# cerebro5_8.net
KiCad netlist of a schematic drawn in EAGLE
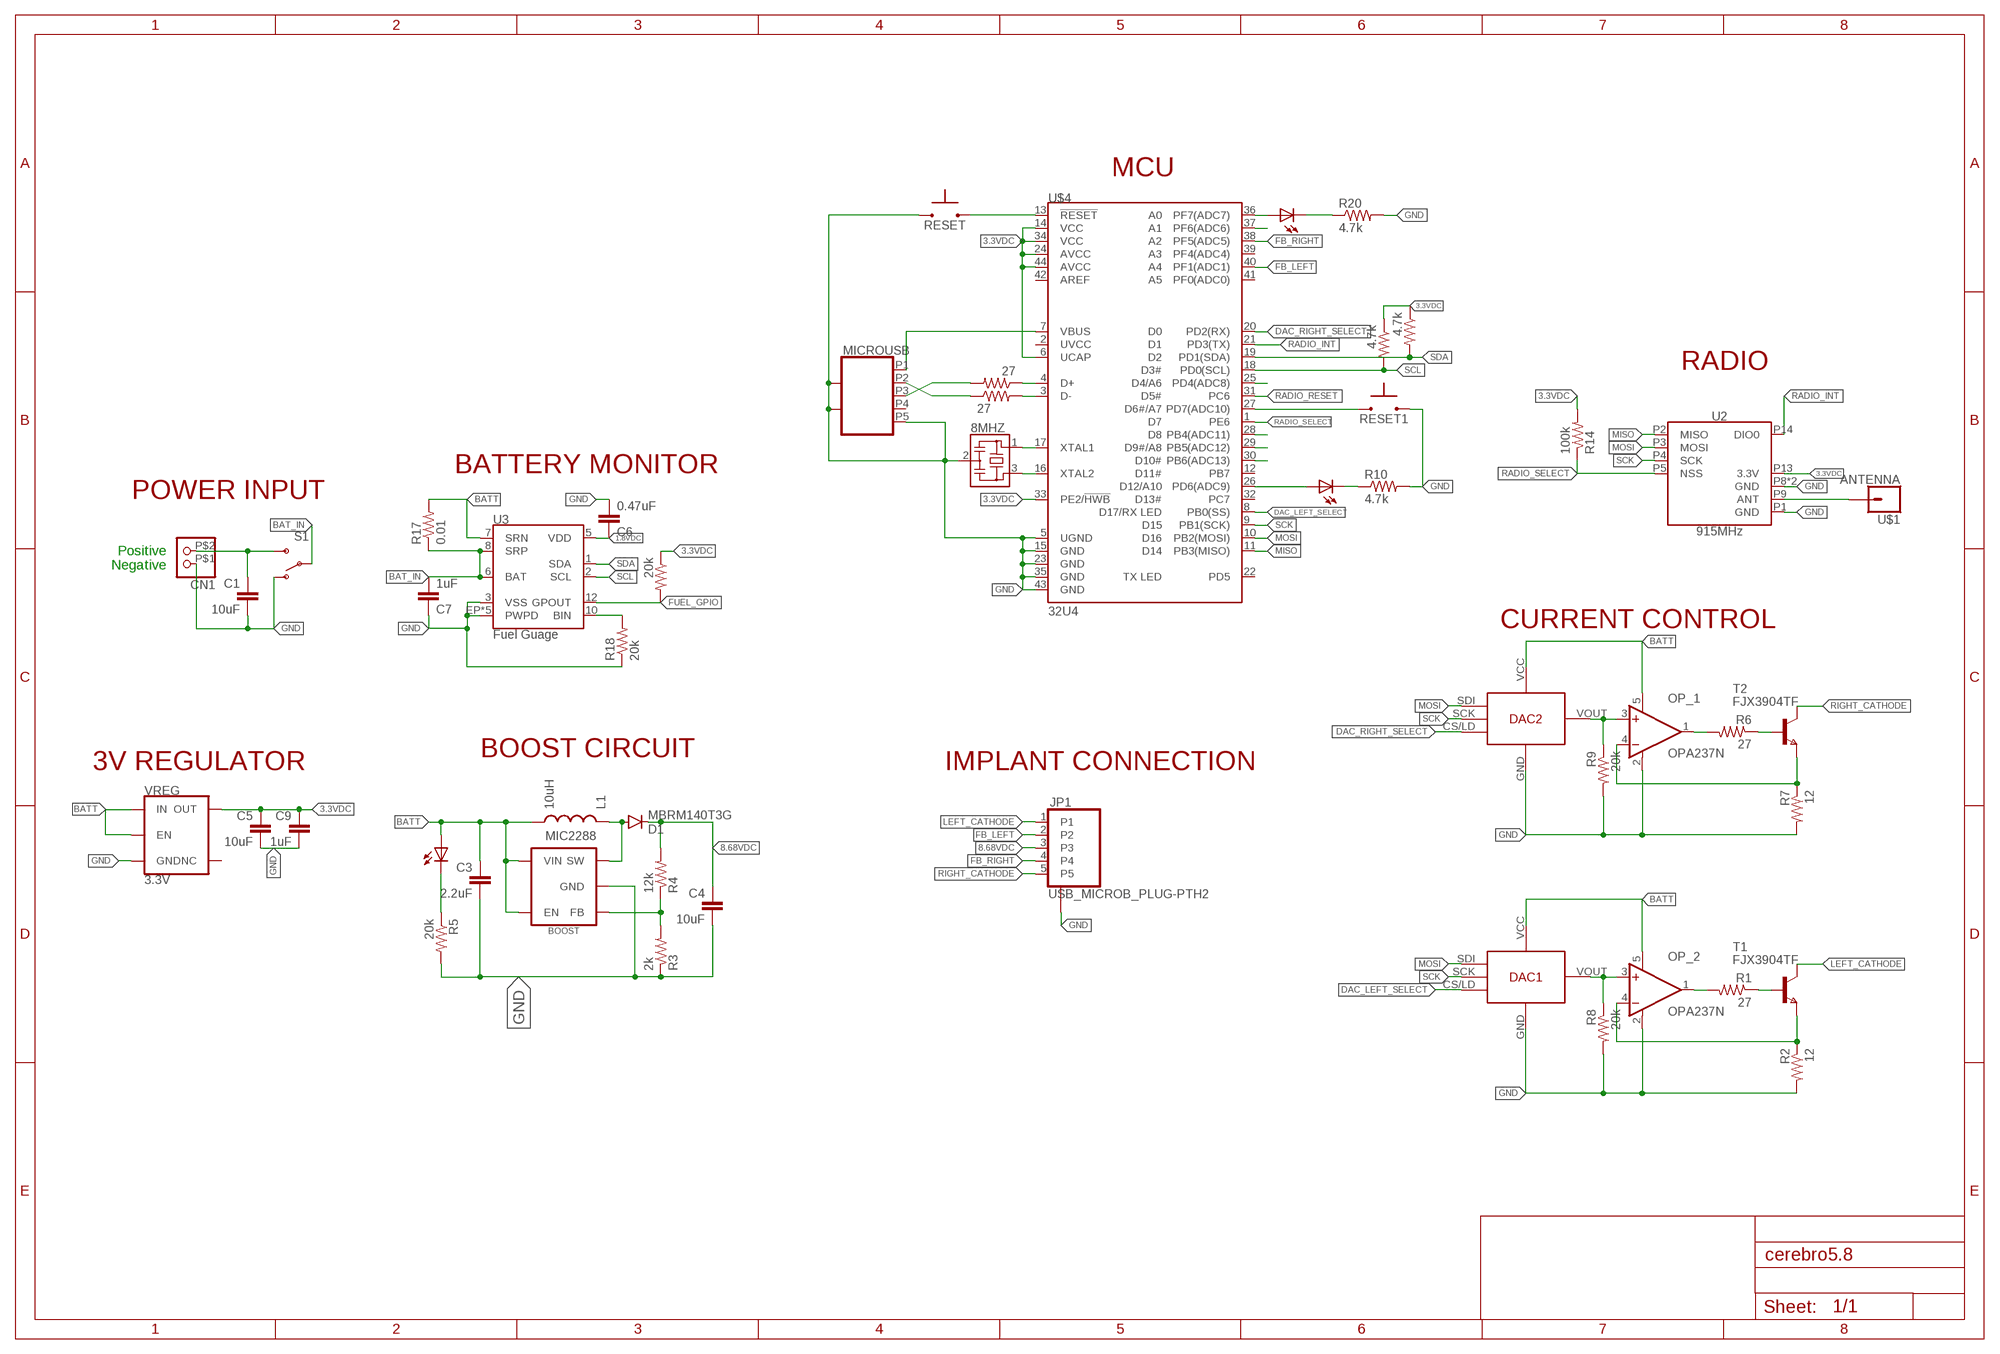
[diagram p0: schematic, sheet 1]

(export (version "E")
  (design (tool "Eeschema 10.0.6"))
  (components
    (comp (ref "8MHZ")
      (value "RESONATOR_CSTCE_V")
      (footprint "eagle-import:CSTCE_V")
      (libsource (lib "eagle-import") (part "RESONATOR_CSTCE_V"))
    )
    (comp (ref "C1")
      (value "10uF")
      (footprint "eagle-import:0805")
      (libsource (lib "eagle-import") (part "10UF-0805-10V-10%"))
    )
    (comp (ref "C3")
      (value "2.2uF")
      (footprint "eagle-import:0805")
      (libsource (lib "eagle-import") (part "2.2UF-0805-25V-(+80/-20%)"))
    )
    (comp (ref "C4")
      (value "10uF")
      (footprint "eagle-import:0805")
      (libsource (lib "eagle-import") (part "10UF-0805-10V-10%"))
    )
    (comp (ref "C5")
      (value "10uF")
      (footprint "eagle-import:0805")
      (libsource (lib "eagle-import") (part "10UF-0805-10V-10%"))
    )
    (comp (ref "C6")
      (value "0.47uF")
      (footprint "eagle-import:0805")
      (libsource (lib "eagle-import") (part "10UF-0805-10V-10%"))
    )
    (comp (ref "C7")
      (value "1uF")
      (footprint "eagle-import:0805")
      (libsource (lib "eagle-import") (part "10UF-0805-10V-10%"))
    )
    (comp (ref "C9")
      (value "1uF")
      (footprint "eagle-import:0805")
      (libsource (lib "eagle-import") (part "10UF-0805-10V-10%"))
    )
    (comp (ref "CN1")
      (value "JST_2PINMICRO")
      (footprint "eagle-import:MICRO_LOCK_2PIN")
      (libsource (lib "eagle-import") (part "JST_2PINMICRO"))
    )
    (comp (ref "D1")
      (value "MBRM140T3G")
      (footprint "eagle-import:POWERMITE")
      (libsource (lib "eagle-import") (part "DIODEPOWERMITE"))
    )
    (comp (ref "DAC1")
      (value "DAC")
      (footprint "eagle-import:SC-70")
      (libsource (lib "eagle-import") (part "DAC_LTC2630"))
    )
    (comp (ref "DAC2")
      (value "DAC")
      (footprint "eagle-import:SC-70")
      (libsource (lib "eagle-import") (part "DAC_LTC2630"))
    )
    (comp (ref "INDICATOR_LED")
      (value "RED")
      (footprint "eagle-import:CHIP-LED0603")
      (libsource (lib "eagle-import") (part "LEDCHIP-LED0603"))
    )
    (comp (ref "INDICATOR_LED1")
      (value "YLW")
      (footprint "eagle-import:CHIP-LED0603")
      (libsource (lib "eagle-import") (part "LEDCHIP-LED0603"))
    )
    (comp (ref "INDICATOR_LED2")
      (value "GRN")
      (footprint "eagle-import:CHIP-LED0603")
      (libsource (lib "eagle-import") (part "LEDCHIP-LED0603"))
    )
    (comp (ref "JP1")
      (value "USB_MICROB_PLUG-PTH2")
      (footprint "eagle-import:MICRO-B-TH")
      (libsource (lib "eagle-import") (part "USB_MICROB_PLUG-PTH2"))
    )
    (comp (ref "L1")
      (value "10uH")
      (footprint "eagle-import:1812")
      (libsource (lib "eagle-import") (part "INDUCTORLQH4"))
    )
    (comp (ref "MIC2288")
      (value "BOOST")
      (footprint "eagle-import:SOT23-5")
      (libsource (lib "eagle-import") (part "BOOST_CONVERTER"))
    )
    (comp (ref "MICROUSB")
      (value "USB_MICRO_SOCKET_HORZ_REINFORCED")
      (footprint "eagle-import:USB_HORZ_REINFORCED_MICRO")
      (libsource (lib "eagle-import") (part "USB_MICRO_SOCKET_HORZ_REINFORCED"))
    )
    (comp (ref "OP_1")
      (value "OPA237N")
      (footprint "eagle-import:SOT23-5")
      (fields (field (name "MF") "TEXAS INSTRUMENTS") (field (name "MPN") "OPA237NA/250"))
      (libsource (lib "eagle-import") (part "OPA237N"))
    )
    (comp (ref "OP_2")
      (value "OPA237N")
      (footprint "eagle-import:SOT23-5")
      (fields (field (name "MF") "TEXAS INSTRUMENTS") (field (name "MPN") "OPA237NA/250"))
      (libsource (lib "eagle-import") (part "OPA237N"))
    )
    (comp (ref "R1")
      (value "27")
      (footprint "eagle-import:0603-RES")
      (libsource (lib "eagle-import") (part "RESISTOR0603-RES"))
    )
    (comp (ref "R2")
      (value "12")
      (footprint "eagle-import:0603-RES")
      (libsource (lib "eagle-import") (part "RESISTOR0603-RES"))
    )
    (comp (ref "R3")
      (value "2k")
      (footprint "eagle-import:0603-RES")
      (libsource (lib "eagle-import") (part "RESISTOR0603-RES"))
    )
    (comp (ref "R4")
      (value "12k")
      (footprint "eagle-import:0805")
      (libsource (lib "eagle-import") (part "RESISTOR0805-RES"))
    )
    (comp (ref "R5")
      (value "20k")
      (footprint "eagle-import:0603-RES")
      (libsource (lib "eagle-import") (part "RESISTOR0603-RES"))
    )
    (comp (ref "R6")
      (value "27")
      (footprint "eagle-import:0603-RES")
      (libsource (lib "eagle-import") (part "RESISTOR0603-RES"))
    )
    (comp (ref "R7")
      (value "12")
      (footprint "eagle-import:0603-RES")
      (libsource (lib "eagle-import") (part "RESISTOR0603-RES"))
    )
    (comp (ref "R8")
      (value "20k")
      (footprint "eagle-import:0603-RES")
      (libsource (lib "eagle-import") (part "RESISTOR0603-RES"))
    )
    (comp (ref "R9")
      (value "20k")
      (footprint "eagle-import:0603-RES")
      (libsource (lib "eagle-import") (part "RESISTOR0603-RES"))
    )
    (comp (ref "R10")
      (value "4.7k")
      (footprint "eagle-import:0603-RES")
      (libsource (lib "eagle-import") (part "RESISTOR0603-RES"))
    )
    (comp (ref "R12")
      (value "27")
      (footprint "eagle-import:0603-RES")
      (libsource (lib "eagle-import") (part "RESISTOR0603-RES"))
    )
    (comp (ref "R13")
      (value "27")
      (footprint "eagle-import:0603-RES")
      (libsource (lib "eagle-import") (part "RESISTOR0603-RES"))
    )
    (comp (ref "R14")
      (value "100k")
      (footprint "eagle-import:0603-RES")
      (libsource (lib "eagle-import") (part "RESISTOR0603-RES"))
    )
    (comp (ref "R15")
      (value "4.7k")
      (footprint "eagle-import:0603-RES")
      (libsource (lib "eagle-import") (part "RESISTOR0603-RES"))
    )
    (comp (ref "R16")
      (value "4.7k")
      (footprint "eagle-import:0603-RES")
      (libsource (lib "eagle-import") (part "RESISTOR0603-RES"))
    )
    (comp (ref "R17")
      (value "0.01")
      (footprint "eagle-import:1206")
      (libsource (lib "eagle-import") (part "RESISTOR1206"))
    )
    (comp (ref "R18")
      (value "20k")
      (footprint "eagle-import:0603-RES")
      (libsource (lib "eagle-import") (part "RESISTOR0603-RES"))
    )
    (comp (ref "R19")
      (value "20k")
      (footprint "eagle-import:0603-RES")
      (libsource (lib "eagle-import") (part "RESISTOR0603-RES"))
    )
    (comp (ref "R20")
      (value "4.7k")
      (footprint "eagle-import:0603-RES")
      (libsource (lib "eagle-import") (part "RESISTOR0603-RES"))
    )
    (comp (ref "RESET")
      (value "SWITCH-MOMENTARY-NO")
      (footprint "eagle-import:SWITCH_MOMENTARY_XS")
      (libsource (lib "eagle-import") (part "SWITCH-MOMENTARY-NO"))
    )
    (comp (ref "RESET1")
      (value "SWITCH-MOMENTARY-NO")
      (footprint "eagle-import:SWITCH_MOMENTARY_XS")
      (libsource (lib "eagle-import") (part "SWITCH-MOMENTARY-NO"))
    )
    (comp (ref "S1")
      (value "SWITCH-SPDTREINFORCED_SMD")
      (footprint "eagle-import:SWITCH-SPDT-SMD-REINFORCED")
      (libsource (lib "eagle-import") (part "SWITCH-SPDTREINFORCED_SMD"))
    )
    (comp (ref "T1")
      (value "FJX3904TF")
      (footprint "eagle-import:SOT323")
      (fields (field (name "MPN") "DSS4160U-7"))
      (libsource (lib "eagle-import") (part "NPNSOT323"))
    )
    (comp (ref "T2")
      (value "FJX3904TF")
      (footprint "eagle-import:SOT323")
      (fields (field (name "MPN") "DSS4160U-7"))
      (libsource (lib "eagle-import") (part "NPNSOT323"))
    )
    (comp (ref "U$1")
      (value "ANTENNA")
      (footprint "eagle-import:1X01")
      (libsource (lib "eagle-import") (part "ANTENNA"))
    )
    (comp (ref "U$4")
      (value "32U4")
      (footprint "eagle-import:QFN-44-NOPAD")
      (libsource (lib "eagle-import") (part "ATMEGA32U4QFN2"))
    )
    (comp (ref "U2")
      (value "915MHz")
      (footprint "eagle-import:RFM69HCW-XXXS2")
      (libsource (lib "eagle-import") (part "RFM69HCW-915"))
    )
    (comp (ref "U3")
      (value "Fuel Guage")
      (footprint "eagle-import:PDSO-N12")
      (libsource (lib "eagle-import") (part "BQ27441-G1"))
    )
    (comp (ref "VREG")
      (value "3.3V")
      (footprint "eagle-import:SOT23-5")
      (libsource (lib "eagle-import") (part "V_REG_AP2112K-3.3V"))
    )
  )
  (nets
    (net (code "1") (name "1.8VDC") (class "Default")
      (node (ref "C6") (pin "1") (pinfunction "1_1") (pintype "passive"))
      (node (ref "U3") (pin "5") (pinfunction "VDD_5") (pintype "bidirectional"))
    )
    (net (code "2") (name "3.3VDC") (class "Default")
      (node (ref "C5") (pin "1") (pinfunction "1_1") (pintype "passive"))
      (node (ref "C9") (pin "1") (pinfunction "1_1") (pintype "passive"))
      (node (ref "R14") (pin "2") (pinfunction "2_2") (pintype "passive"))
      (node (ref "R15") (pin "1") (pinfunction "1_1") (pintype "passive"))
      (node (ref "R16") (pin "1") (pinfunction "1_1") (pintype "passive"))
      (node (ref "R19") (pin "1") (pinfunction "1_1") (pintype "passive"))
      (node (ref "U$4") (pin "14") (pinfunction "VCC_14") (pintype "bidirectional"))
      (node (ref "U$4") (pin "24") (pinfunction "AVCC_24") (pintype "bidirectional"))
      (node (ref "U$4") (pin "33") (pinfunction "PE2/~{HWB}_33") (pintype "bidirectional"))
      (node (ref "U$4") (pin "34") (pinfunction "VCC_34") (pintype "bidirectional"))
      (node (ref "U$4") (pin "44") (pinfunction "AVCC_44") (pintype "bidirectional"))
      (node (ref "U$4") (pin "6") (pinfunction "UCAP_6") (pintype "bidirectional"))
      (node (ref "U2") (pin "P13") (pinfunction "3.3V_P13") (pintype "power_in"))
      (node (ref "VREG") (pin "5") (pinfunction "OUT_5") (pintype "passive"))
    )
    (net (code "3") (name "8.68VDC") (class "Default")
      (node (ref "C4") (pin "1") (pinfunction "1_1") (pintype "passive"))
      (node (ref "D1") (pin "CATHODE") (pinfunction "C_CATHODE") (pintype "passive"))
      (node (ref "JP1") (pin "3") (pinfunction "P3_3") (pintype "bidirectional"))
      (node (ref "R4") (pin "2") (pinfunction "2_2") (pintype "passive"))
    )
    (net (code "4") (name "BATT") (class "Default")
      (node (ref "C3") (pin "1") (pinfunction "1_1") (pintype "passive"))
      (node (ref "DAC1") (pin "VCC") (pinfunction "VIN_VCC") (pintype "bidirectional"))
      (node (ref "DAC2") (pin "VCC") (pinfunction "VIN_VCC") (pintype "bidirectional"))
      (node (ref "INDICATOR_LED") (pin "A") (pinfunction "A_A") (pintype "passive"))
      (node (ref "L1") (pin "P$2") (pinfunction "2_P$2") (pintype "passive"))
      (node (ref "L1") (pin "P$4") (pinfunction "2_P$4") (pintype "passive"))
      (node (ref "MIC2288") (pin "4") (pinfunction "EN_4") (pintype "input"))
      (node (ref "MIC2288") (pin "5") (pinfunction "VIN_5") (pintype "passive"))
      (node (ref "OP_1") (pin "5") (pinfunction "V+_5") (pintype "power_in"))
      (node (ref "OP_2") (pin "5") (pinfunction "V+_5") (pintype "power_in"))
      (node (ref "R17") (pin "2") (pinfunction "2_2") (pintype "passive"))
      (node (ref "U3") (pin "7") (pinfunction "SRN_7") (pintype "bidirectional"))
      (node (ref "VREG") (pin "1") (pinfunction "IN_1") (pintype "input"))
      (node (ref "VREG") (pin "3") (pinfunction "EN_3") (pintype "input"))
    )
    (net (code "5") (name "BAT_IN") (class "Default")
      (node (ref "C7") (pin "2") (pinfunction "2_2") (pintype "passive"))
      (node (ref "R17") (pin "1") (pinfunction "1_1") (pintype "passive"))
      (node (ref "S1") (pin "2") (pinfunction "P_2") (pintype "passive"))
      (node (ref "U3") (pin "6") (pinfunction "BAT_6") (pintype "bidirectional"))
      (node (ref "U3") (pin "8") (pinfunction "SRP_8") (pintype "bidirectional"))
    )
    (net (code "6") (name "DAC_LEFT_SELECT") (class "Default")
      (node (ref "DAC1") (pin "CS/LD") (pinfunction "CS/LD_CS/LD") (pintype "bidirectional"))
      (node (ref "U$4") (pin "8") (pinfunction "PB0(SS)_8") (pintype "bidirectional"))
    )
    (net (code "7") (name "DAC_RIGHT_SELECT") (class "Default")
      (node (ref "DAC2") (pin "CS/LD") (pinfunction "CS/LD_CS/LD") (pintype "bidirectional"))
      (node (ref "U$4") (pin "20") (pinfunction "PD2(RX)_20") (pintype "bidirectional"))
    )
    (net (code "8") (name "FB_LEFT") (class "Default")
      (node (ref "JP1") (pin "2") (pinfunction "P2_2") (pintype "bidirectional"))
      (node (ref "U$4") (pin "40") (pinfunction "PF1(ADC1)_40") (pintype "bidirectional"))
    )
    (net (code "9") (name "FB_RIGHT") (class "Default")
      (node (ref "JP1") (pin "4") (pinfunction "P4_4") (pintype "bidirectional"))
      (node (ref "U$4") (pin "38") (pinfunction "PF5(ADC5)_38") (pintype "bidirectional"))
    )
    (net (code "10") (name "FUEL_GPIO") (class "Default")
      (node (ref "R19") (pin "2") (pinfunction "2_2") (pintype "passive"))
      (node (ref "U3") (pin "12") (pinfunction "GPOUT_12") (pintype "bidirectional"))
    )
    (net (code "11") (name "GND") (class "Default")
      (node (ref "8MHZ") (pin "2") (pinfunction "2_2") (pintype "passive"))
      (node (ref "C1") (pin "2") (pinfunction "2_2") (pintype "passive"))
      (node (ref "C3") (pin "2") (pinfunction "2_2") (pintype "passive"))
      (node (ref "C4") (pin "2") (pinfunction "2_2") (pintype "passive"))
      (node (ref "C5") (pin "2") (pinfunction "2_2") (pintype "passive"))
      (node (ref "C6") (pin "2") (pinfunction "2_2") (pintype "passive"))
      (node (ref "C7") (pin "1") (pinfunction "1_1") (pintype "passive"))
      (node (ref "C9") (pin "2") (pinfunction "2_2") (pintype "passive"))
      (node (ref "CN1") (pin "P$1") (pinfunction "1_P$1") (pintype "passive"))
      (node (ref "DAC1") (pin "GND") (pinfunction "GND_GND") (pintype "bidirectional"))
      (node (ref "DAC2") (pin "GND") (pinfunction "GND_GND") (pintype "bidirectional"))
      (node (ref "JP1") (pin "P$1") (pinfunction "GND_PINS_P$1") (pintype "bidirectional"))
      (node (ref "JP1") (pin "P$2") (pinfunction "GND_PINS_P$2") (pintype "bidirectional"))
      (node (ref "MIC2288") (pin "2") (pinfunction "GND_2") (pintype "input"))
      (node (ref "MICROUSB") (pin "G1") (pinfunction "P$1_G1") (pintype "bidirectional"))
      (node (ref "MICROUSB") (pin "G2") (pinfunction "P$1_G2") (pintype "bidirectional"))
      (node (ref "MICROUSB") (pin "P$1") (pinfunction "P$2_P$1") (pintype "bidirectional"))
      (node (ref "MICROUSB") (pin "P$2") (pinfunction "P$2_P$2") (pintype "bidirectional"))
      (node (ref "MICROUSB") (pin "P5") (pinfunction "P5_P5") (pintype "bidirectional"))
      (node (ref "OP_1") (pin "2") (pinfunction "V-_2") (pintype "power_in"))
      (node (ref "OP_2") (pin "2") (pinfunction "V-_2") (pintype "power_in"))
      (node (ref "R10") (pin "2") (pinfunction "2_2") (pintype "passive"))
      (node (ref "R18") (pin "1") (pinfunction "1_1") (pintype "passive"))
      (node (ref "R2") (pin "2") (pinfunction "2_2") (pintype "passive"))
      (node (ref "R20") (pin "2") (pinfunction "2_2") (pintype "passive"))
      (node (ref "R3") (pin "1") (pinfunction "1_1") (pintype "passive"))
      (node (ref "R5") (pin "2") (pinfunction "2_2") (pintype "passive"))
      (node (ref "R7") (pin "2") (pinfunction "2_2") (pintype "passive"))
      (node (ref "R8") (pin "2") (pinfunction "2_2") (pintype "passive"))
      (node (ref "R9") (pin "2") (pinfunction "2_2") (pintype "passive"))
      (node (ref "RESET") (pin "P$1") (pinfunction "1_P$1") (pintype "bidirectional"))
      (node (ref "RESET1") (pin "P$2") (pinfunction "2_P$2") (pintype "bidirectional"))
      (node (ref "S1") (pin "1") (pinfunction "O_1") (pintype "passive"))
      (node (ref "U$4") (pin "15") (pinfunction "GND_15") (pintype "bidirectional"))
      (node (ref "U$4") (pin "23") (pinfunction "GND_23") (pintype "bidirectional"))
      (node (ref "U$4") (pin "35") (pinfunction "GND_35") (pintype "bidirectional"))
      (node (ref "U$4") (pin "43") (pinfunction "GND_43") (pintype "bidirectional"))
      (node (ref "U$4") (pin "5") (pinfunction "UGND_5") (pintype "bidirectional"))
      (node (ref "U2") (pin "P1") (pinfunction "GND_P1") (pintype "power_in"))
      (node (ref "U2") (pin "P10") (pinfunction "GND_P10") (pintype "power_in"))
      (node (ref "U2") (pin "P8") (pinfunction "GND_P8") (pintype "power_in"))
      (node (ref "U3") (pin "3") (pinfunction "VSS_3") (pintype "bidirectional"))
      (node (ref "U3") (pin "EP") (pinfunction "PWPD_EP") (pintype "bidirectional"))
      (node (ref "U3") (pin "EP1") (pinfunction "PWPD_EP1") (pintype "bidirectional"))
      (node (ref "U3") (pin "EP2") (pinfunction "PWPD_EP2") (pintype "bidirectional"))
      (node (ref "U3") (pin "EP3") (pinfunction "PWPD_EP3") (pintype "bidirectional"))
      (node (ref "U3") (pin "EP4") (pinfunction "PWPD_EP4") (pintype "bidirectional"))
      (node (ref "VREG") (pin "2") (pinfunction "GND_2") (pintype "input"))
    )
    (net (code "12") (name "LEFT_CATHODE") (class "Default")
      (node (ref "JP1") (pin "1") (pinfunction "P1_1") (pintype "bidirectional"))
      (node (ref "T1") (pin "1") (pinfunction "C_1") (pintype "passive"))
    )
    (net (code "13") (name "MISO") (class "Default")
      (node (ref "U$4") (pin "11") (pinfunction "PB3(MISO)_11") (pintype "bidirectional"))
      (node (ref "U2") (pin "P2") (pinfunction "MISO_P2") (pintype "bidirectional"))
    )
    (net (code "14") (name "MOSI") (class "Default")
      (node (ref "DAC1") (pin "SDI") (pinfunction "SDI_SDI") (pintype "bidirectional"))
      (node (ref "DAC2") (pin "SDI") (pinfunction "SDI_SDI") (pintype "bidirectional"))
      (node (ref "U$4") (pin "10") (pinfunction "PB2(MOSI)_10") (pintype "bidirectional"))
      (node (ref "U2") (pin "P3") (pinfunction "MOSI_P3") (pintype "input"))
    )
    (net (code "15") (name "Net-(CN1-2)") (class "Default")
      (node (ref "C1") (pin "1") (pinfunction "1_1") (pintype "passive"))
      (node (ref "CN1") (pin "P$2") (pinfunction "2_P$2") (pintype "passive"))
      (node (ref "S1") (pin "3") (pinfunction "S_3") (pintype "passive"))
    )
    (net (code "16") (name "Net-(D1-A)") (class "Default")
      (node (ref "D1") (pin "ANODE") (pinfunction "A_ANODE") (pintype "passive"))
      (node (ref "L1") (pin "P$1") (pinfunction "1_P$1") (pintype "passive"))
      (node (ref "L1") (pin "P$3") (pinfunction "1_P$3") (pintype "passive"))
      (node (ref "MIC2288") (pin "1") (pinfunction "SW_1") (pintype "input"))
    )
    (net (code "17") (name "Net-(INDICATOR_LED-PadC)") (class "Default")
      (node (ref "INDICATOR_LED") (pin "C") (pinfunction "C_C") (pintype "passive"))
      (node (ref "R5") (pin "1") (pinfunction "1_1") (pintype "passive"))
    )
    (net (code "18") (name "Net-(INDICATOR_LED1-PadC)") (class "Default")
      (node (ref "INDICATOR_LED1") (pin "C") (pinfunction "C_C") (pintype "passive"))
      (node (ref "R20") (pin "1") (pinfunction "1_1") (pintype "passive"))
    )
    (net (code "19") (name "Net-(INDICATOR_LED2-PadC)") (class "Default")
      (node (ref "INDICATOR_LED2") (pin "C") (pinfunction "C_C") (pintype "passive"))
      (node (ref "R10") (pin "1") (pinfunction "1_1") (pintype "passive"))
    )
    (net (code "20") (name "Net-(MIC2288-FB)") (class "Default")
      (node (ref "MIC2288") (pin "3") (pinfunction "FB_3") (pintype "input"))
      (node (ref "R3") (pin "2") (pinfunction "2_2") (pintype "passive"))
      (node (ref "R4") (pin "1") (pinfunction "1_1") (pintype "passive"))
    )
    (net (code "21") (name "Net-(MICROUSB-PadP2)") (class "Default")
      (node (ref "MICROUSB") (pin "P2") (pinfunction "P2_P2") (pintype "bidirectional"))
      (node (ref "R13") (pin "1") (pinfunction "1_1") (pintype "passive"))
    )
    (net (code "22") (name "Net-(MICROUSB-PadP3)") (class "Default")
      (node (ref "MICROUSB") (pin "P3") (pinfunction "P3_P3") (pintype "bidirectional"))
      (node (ref "R12") (pin "2") (pinfunction "2_2") (pintype "passive"))
    )
    (net (code "23") (name "Net-(OP_1-+IN)") (class "Default")
      (node (ref "DAC2") (pin "VOUT") (pinfunction "VOUT_VOUT") (pintype "bidirectional"))
      (node (ref "OP_1") (pin "3") (pinfunction "+IN_3") (pintype "input"))
      (node (ref "R9") (pin "1") (pinfunction "1_1") (pintype "passive"))
    )
    (net (code "24") (name "Net-(OP_1--IN)") (class "Default")
      (node (ref "OP_1") (pin "4") (pinfunction "-IN_4") (pintype "input"))
      (node (ref "R7") (pin "1") (pinfunction "1_1") (pintype "passive"))
      (node (ref "T2") (pin "3") (pinfunction "E_3") (pintype "passive"))
    )
    (net (code "25") (name "Net-(OP_1-OUT)") (class "Default")
      (node (ref "OP_1") (pin "1") (pinfunction "OUT_1") (pintype "output"))
      (node (ref "R6") (pin "2") (pinfunction "2_2") (pintype "passive"))
    )
    (net (code "26") (name "Net-(OP_2-+IN)") (class "Default")
      (node (ref "DAC1") (pin "VOUT") (pinfunction "VOUT_VOUT") (pintype "bidirectional"))
      (node (ref "OP_2") (pin "3") (pinfunction "+IN_3") (pintype "input"))
      (node (ref "R8") (pin "1") (pinfunction "1_1") (pintype "passive"))
    )
    (net (code "27") (name "Net-(OP_2--IN)") (class "Default")
      (node (ref "OP_2") (pin "4") (pinfunction "-IN_4") (pintype "input"))
      (node (ref "R2") (pin "1") (pinfunction "1_1") (pintype "passive"))
      (node (ref "T1") (pin "3") (pinfunction "E_3") (pintype "passive"))
    )
    (net (code "28") (name "Net-(OP_2-OUT)") (class "Default")
      (node (ref "OP_2") (pin "1") (pinfunction "OUT_1") (pintype "output"))
      (node (ref "R1") (pin "2") (pinfunction "2_2") (pintype "passive"))
    )
    (net (code "29") (name "Net-(RESET-2)") (class "Default")
      (node (ref "RESET") (pin "P$2") (pinfunction "2_P$2") (pintype "bidirectional"))
      (node (ref "U$4") (pin "13") (pinfunction "~{RESET}_13") (pintype "bidirectional"))
    )
    (net (code "30") (name "Net-(RESET1-1)") (class "Default")
      (node (ref "RESET1") (pin "P$1") (pinfunction "1_P$1") (pintype "bidirectional"))
      (node (ref "U$4") (pin "27") (pinfunction "PD7(ADC10)_27") (pintype "bidirectional"))
    )
    (net (code "31") (name "Net-(T1-B)") (class "Default")
      (node (ref "R1") (pin "1") (pinfunction "1_1") (pintype "passive"))
      (node (ref "T1") (pin "2") (pinfunction "B_2") (pintype "passive"))
    )
    (net (code "32") (name "Net-(T2-B)") (class "Default")
      (node (ref "R6") (pin "1") (pinfunction "1_1") (pintype "passive"))
      (node (ref "T2") (pin "2") (pinfunction "B_2") (pintype "passive"))
    )
    (net (code "33") (name "Net-(U$4-D+)") (class "Default")
      (node (ref "R12") (pin "1") (pinfunction "1_1") (pintype "passive"))
      (node (ref "U$4") (pin "4") (pinfunction "D+_4") (pintype "bidirectional"))
    )
    (net (code "34") (name "Net-(U$4-D-)") (class "Default")
      (node (ref "R13") (pin "2") (pinfunction "2_2") (pintype "passive"))
      (node (ref "U$4") (pin "3") (pinfunction "D-_3") (pintype "bidirectional"))
    )
    (net (code "35") (name "Net-(U$4-PD6(ADC9))") (class "Default")
      (node (ref "INDICATOR_LED2") (pin "A") (pinfunction "A_A") (pintype "passive"))
      (node (ref "U$4") (pin "26") (pinfunction "PD6(ADC9)_26") (pintype "bidirectional"))
    )
    (net (code "36") (name "Net-(U$4-PF7(ADC7))") (class "Default")
      (node (ref "INDICATOR_LED1") (pin "A") (pinfunction "A_A") (pintype "passive"))
      (node (ref "U$4") (pin "36") (pinfunction "PF7(ADC7)_36") (pintype "bidirectional"))
    )
    (net (code "37") (name "Net-(U$4-VBUS)") (class "Default")
      (node (ref "MICROUSB") (pin "P1") (pinfunction "P1_P1") (pintype "bidirectional"))
      (node (ref "U$4") (pin "7") (pinfunction "VBUS_7") (pintype "bidirectional"))
    )
    (net (code "38") (name "Net-(U$4-XTAL1)") (class "Default")
      (node (ref "8MHZ") (pin "1") (pinfunction "1_1") (pintype "passive"))
      (node (ref "U$4") (pin "17") (pinfunction "XTAL1_17") (pintype "bidirectional"))
    )
    (net (code "39") (name "Net-(U$4-XTAL2)") (class "Default")
      (node (ref "8MHZ") (pin "3") (pinfunction "3_3") (pintype "passive"))
      (node (ref "U$4") (pin "16") (pinfunction "XTAL2_16") (pintype "bidirectional"))
    )
    (net (code "40") (name "Net-(U2-ANT)") (class "Default")
      (node (ref "U$1") (pin "1") (pinfunction "1_1") (pintype "passive"))
      (node (ref "U2") (pin "P9") (pinfunction "ANT_P9") (pintype "passive"))
    )
    (net (code "41") (name "Net-(U3-BIN)") (class "Default")
      (node (ref "R18") (pin "2") (pinfunction "2_2") (pintype "passive"))
      (node (ref "U3") (pin "10") (pinfunction "BIN_10") (pintype "bidirectional"))
    )
    (net (code "42") (name "RADIO_INT") (class "Default")
      (node (ref "U$4") (pin "21") (pinfunction "PD3(TX)_21") (pintype "bidirectional"))
      (node (ref "U2") (pin "P14") (pinfunction "DIO0_P14") (pintype "bidirectional"))
    )
    (net (code "43") (name "RADIO_RESET") (class "Default")
      (node (ref "U$4") (pin "31") (pinfunction "PC6_31") (pintype "bidirectional"))
    )
    (net (code "44") (name "RADIO_SELECT") (class "Default")
      (node (ref "R14") (pin "1") (pinfunction "1_1") (pintype "passive"))
      (node (ref "U$4") (pin "1") (pinfunction "PE6_1") (pintype "bidirectional"))
      (node (ref "U2") (pin "P5") (pinfunction "NSS_P5") (pintype "input"))
    )
    (net (code "45") (name "RIGHT_CATHODE") (class "Default")
      (node (ref "JP1") (pin "5") (pinfunction "P5_5") (pintype "bidirectional"))
      (node (ref "T2") (pin "1") (pinfunction "C_1") (pintype "passive"))
    )
    (net (code "46") (name "SCK") (class "Default")
      (node (ref "DAC1") (pin "SCK") (pinfunction "SCK_SCK") (pintype "bidirectional"))
      (node (ref "DAC2") (pin "SCK") (pinfunction "SCK_SCK") (pintype "bidirectional"))
      (node (ref "U$4") (pin "9") (pinfunction "PB1(SCK)_9") (pintype "bidirectional"))
      (node (ref "U2") (pin "P4") (pinfunction "SCK_P4") (pintype "input"))
    )
    (net (code "47") (name "SCL") (class "Default")
      (node (ref "R15") (pin "2") (pinfunction "2_2") (pintype "passive"))
      (node (ref "U$4") (pin "18") (pinfunction "PD0(SCL)_18") (pintype "bidirectional"))
      (node (ref "U3") (pin "2") (pinfunction "SCL_2") (pintype "bidirectional"))
    )
    (net (code "48") (name "SDA") (class "Default")
      (node (ref "R16") (pin "2") (pinfunction "2_2") (pintype "passive"))
      (node (ref "U$4") (pin "19") (pinfunction "PD1(SDA)_19") (pintype "bidirectional"))
      (node (ref "U3") (pin "1") (pinfunction "SDA_1") (pintype "bidirectional"))
    )
    (net (code "49") (name "unconnected-(MICROUSB-PadP4)") (class "Default")
      (node (ref "MICROUSB") (pin "P4") (pinfunction "P4_P4") (pintype "bidirectional"))
    )
    (net (code "50") (name "unconnected-(U$4-AREF-Pad42)") (class "Default")
      (node (ref "U$4") (pin "42") (pinfunction "AREF_42") (pintype "bidirectional"))
    )
    (net (code "51") (name "unconnected-(U$4-PB4(ADC11)-Pad28)") (class "Default")
      (node (ref "U$4") (pin "28") (pinfunction "PB4(ADC11)_28") (pintype "bidirectional"))
    )
    (net (code "52") (name "unconnected-(U$4-PB5(ADC12)-Pad29)") (class "Default")
      (node (ref "U$4") (pin "29") (pinfunction "PB5(ADC12)_29") (pintype "bidirectional"))
    )
    (net (code "53") (name "unconnected-(U$4-PB6(ADC13)-Pad30)") (class "Default")
      (node (ref "U$4") (pin "30") (pinfunction "PB6(ADC13)_30") (pintype "bidirectional"))
    )
    (net (code "54") (name "unconnected-(U$4-PB7-Pad12)") (class "Default")
      (node (ref "U$4") (pin "12") (pinfunction "PB7_12") (pintype "bidirectional"))
    )
    (net (code "55") (name "unconnected-(U$4-PC7-Pad32)") (class "Default")
      (node (ref "U$4") (pin "32") (pinfunction "PC7_32") (pintype "bidirectional"))
    )
    (net (code "56") (name "unconnected-(U$4-PD4(ADC8)-Pad25)") (class "Default")
      (node (ref "U$4") (pin "25") (pinfunction "PD4(ADC8)_25") (pintype "bidirectional"))
    )
    (net (code "57") (name "unconnected-(U$4-PD5-Pad22)") (class "Default")
      (node (ref "U$4") (pin "22") (pinfunction "PD5_22") (pintype "bidirectional"))
    )
    (net (code "58") (name "unconnected-(U$4-PF0(ADC0)-Pad41)") (class "Default")
      (node (ref "U$4") (pin "41") (pinfunction "PF0(ADC0)_41") (pintype "bidirectional"))
    )
    (net (code "59") (name "unconnected-(U$4-PF4(ADC4)-Pad39)") (class "Default")
      (node (ref "U$4") (pin "39") (pinfunction "PF4(ADC4)_39") (pintype "bidirectional"))
    )
    (net (code "60") (name "unconnected-(U$4-PF6(ADC6)-Pad37)") (class "Default")
      (node (ref "U$4") (pin "37") (pinfunction "PF6(ADC6)_37") (pintype "bidirectional"))
    )
    (net (code "61") (name "unconnected-(U$4-UVCC-Pad2)") (class "Default")
      (node (ref "U$4") (pin "2") (pinfunction "UVCC_2") (pintype "bidirectional"))
    )
    (net (code "62") (name "unconnected-(VREG-NC-Pad4)") (class "Default")
      (node (ref "VREG") (pin "4") (pinfunction "NC_4") (pintype "no_connect"))
    )
  )
)
